# Ricky_and_Min_Lin_-_ART_Robot.net
KiCad netlist of a schematic drawn in Altium Designer
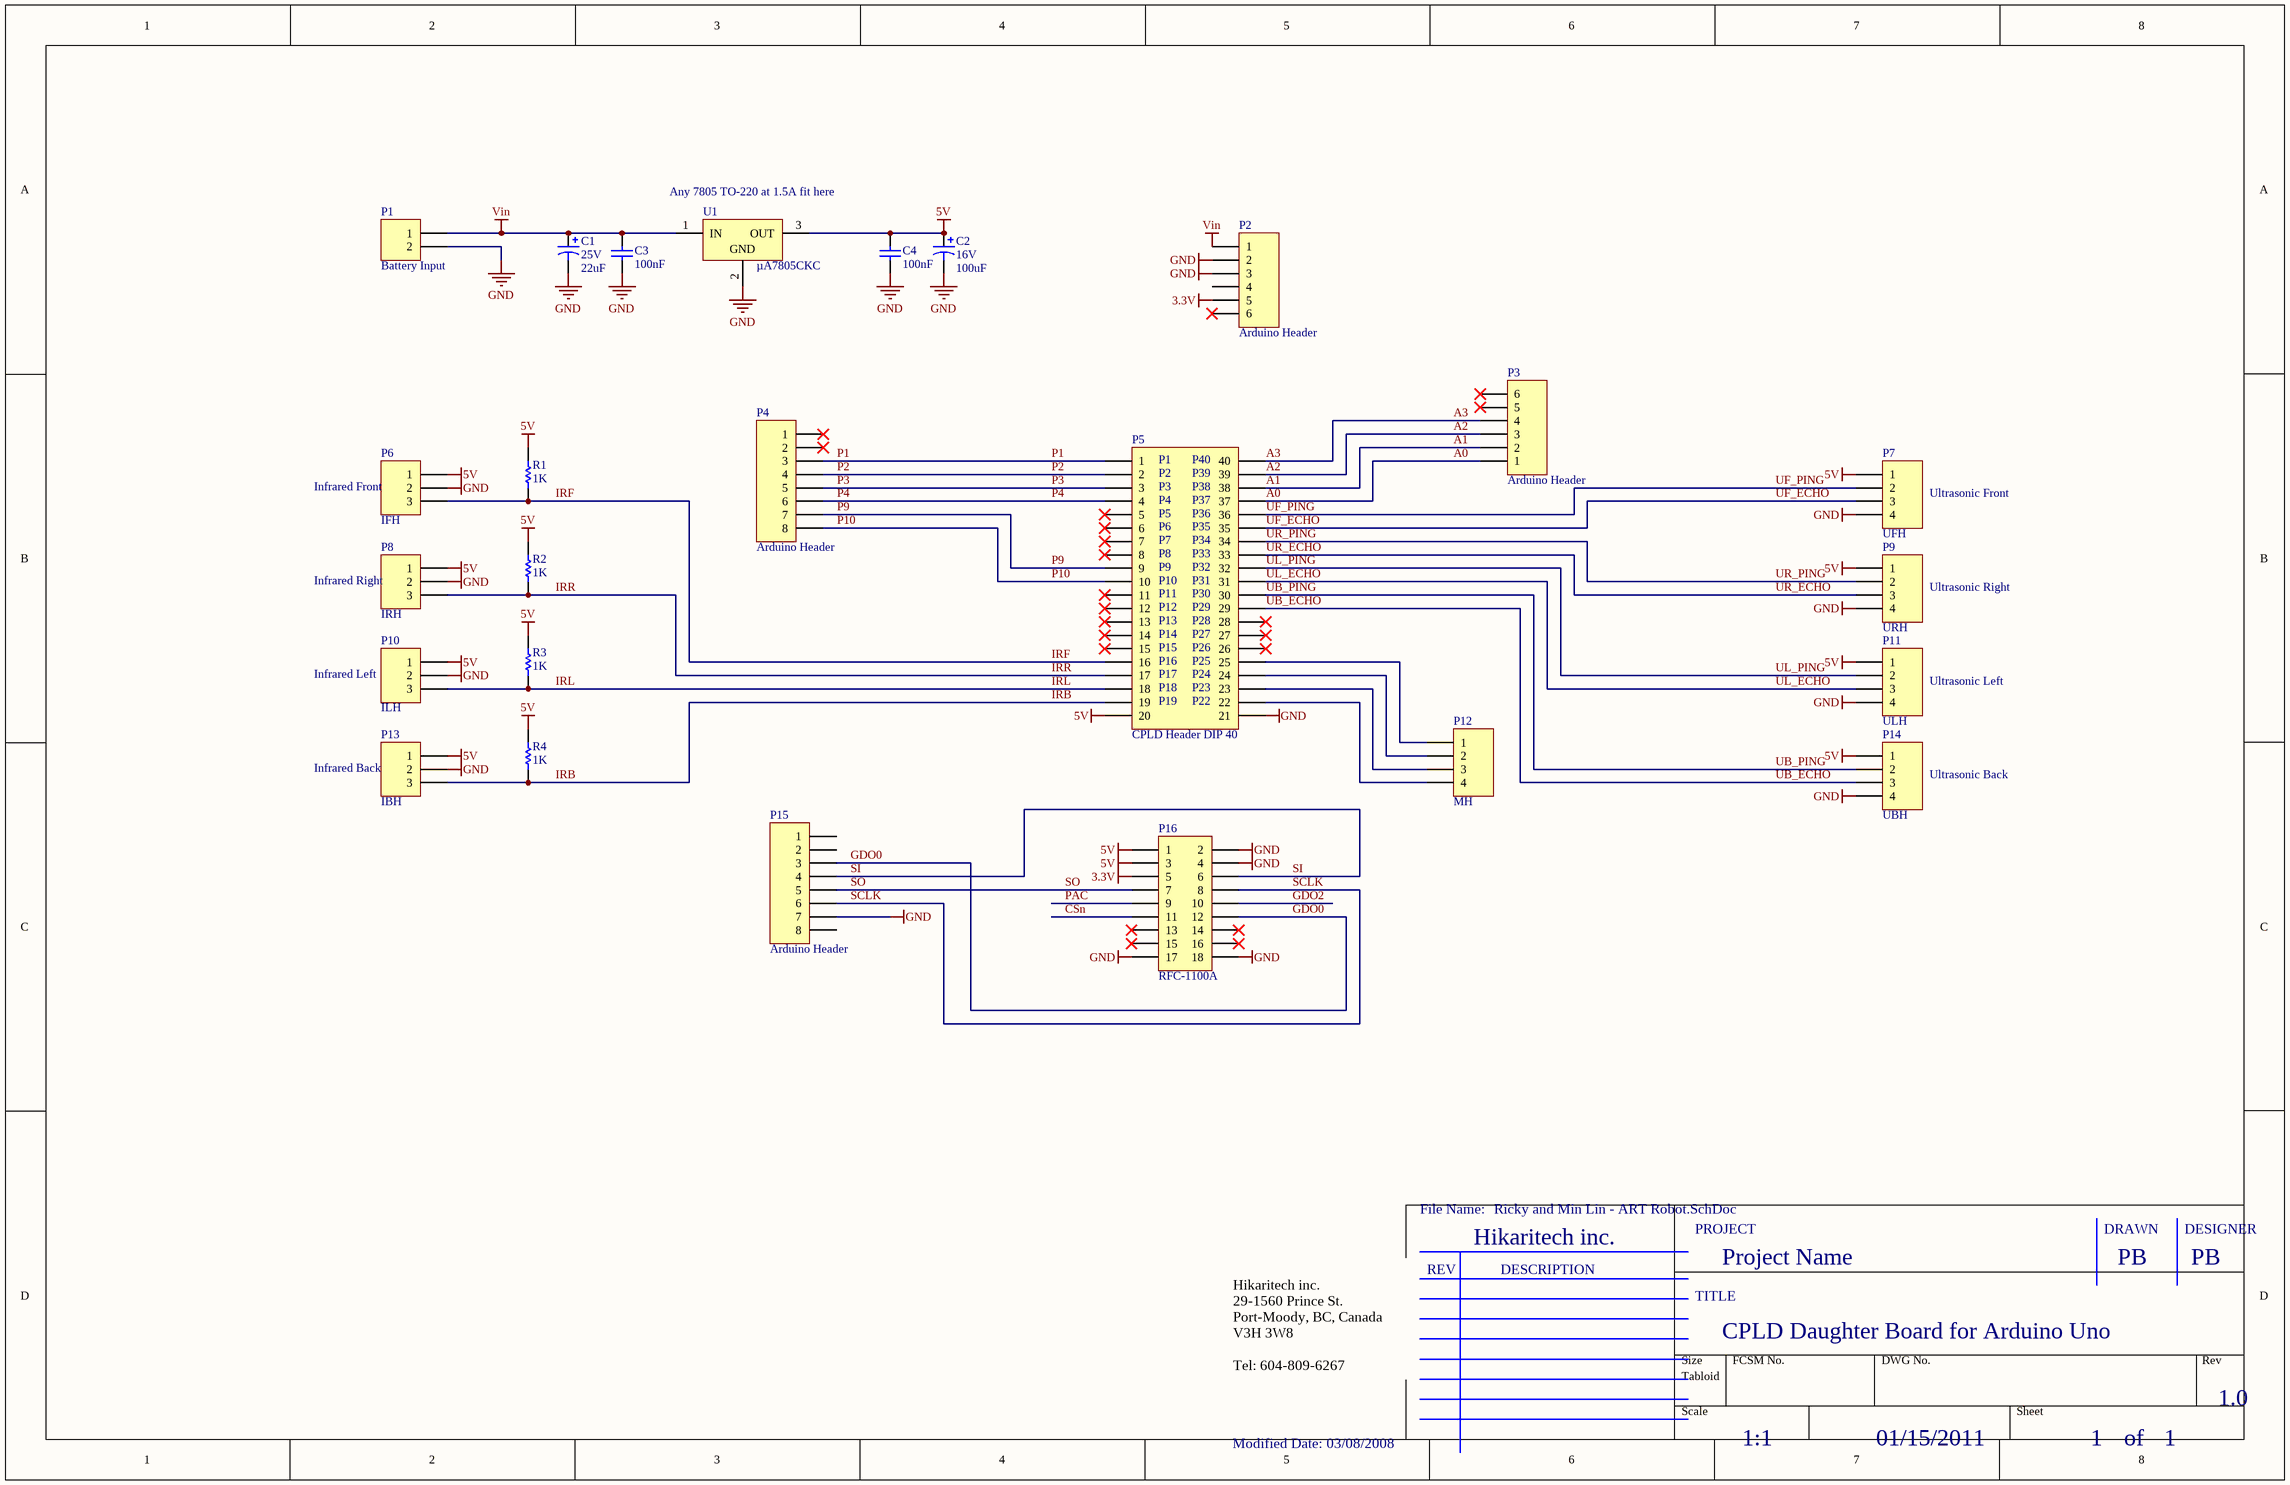
[diagram p0: Ricky and Min Lin - ART Robot.SchDoc]

(export (version "E")
  (design (tool "Eeschema 10.0.6"))
  (components
    (comp (ref "C1")
      (value "25V")
      (footprint "E")
      (description "Solid Aluminum Capacitor with Organic Semiconductor Electrolyte: 22uF, 25V, Bulk Pack")
      (fields (field (name "ALTIUM_VALUE") "22uF") (field (name "PUBLISHER") "Altium Limited"))
      (libsource (lib "Vishay Electrolytic Radial-Lead Capacitor") (part "94SC226X0025EBP"))
    )
    (comp (ref "C2")
      (value "16V")
      (footprint "E")
      (description "Solid Aluminum Capacitor with Organic Semiconductor Electrolyte: 100uF, 16V, Bulk Pack")
      (fields (field (name "ALTIUM_VALUE") "100uF") (field (name "PUBLISHER") "Altium Limited"))
      (libsource (lib "Vishay Electrolytic Radial-Lead Capacitor") (part "94SH107X0016EBP"))
    )
    (comp (ref "C3")
      (value "100nF")
      (footprint "VP41-2.5")
      (description "Dipped Radial Multilayer Ceramic Capacitor X7R: 100nF")
      (fields (field (name "Comment") "VP41BY104") (field (name "PUBLISHER") "Altium Limited"))
      (libsource (lib "Vishay Vitramon Ceramic Dipped Capacitor") (part "VP41BY104"))
    )
    (comp (ref "C4")
      (value "100nF")
      (footprint "VP41-2.5")
      (description "Dipped Radial Multilayer Ceramic Capacitor X7R: 100nF")
      (fields (field (name "Comment") "VP41BY104") (field (name "PUBLISHER") "Altium Limited"))
      (libsource (lib "Vishay Vitramon Ceramic Dipped Capacitor") (part "VP41BY104"))
    )
    (comp (ref "P1")
      (value "Battery Input")
      (footprint "HDR1X2H")
      (description "CONN 2 PINS 2.54mm Wire to Board Latch RA Tin")
      (fields (field (name "MANUFACTURER") "CKMOLD") (field (name "MANUFACTURER PART NUMBER") "25430202"))
      (libsource (lib "ART Robot") (part "CONN 2 PIN 2.54mm Latch RA Tin"))
    )
    (comp (ref "P2")
      (value "Arduino Header")
      (footprint "HDR1X6")
      (description "Header, 6-Pin")
      (fields (field (name "PUBLISHER") "Altium Limited"))
      (libsource (lib "Miscellaneous Connectors") (part "Header 6"))
    )
    (comp (ref "P3")
      (value "Arduino Header")
      (footprint "HDR1X6")
      (description "Header, 6-Pin")
      (fields (field (name "PUBLISHER") "Altium Limited"))
      (libsource (lib "") (part "Header 6_1"))
    )
    (comp (ref "P4")
      (value "Arduino Header")
      (footprint "HDR1X8")
      (description "Header, 8-Pin")
      (fields (field (name "PUBLISHER") "Altium Limited"))
      (libsource (lib "Miscellaneous Connectors") (part "Header 8"))
    )
    (comp (ref "P5")
      (value "CPLD Header DIP 40")
      (footprint "DIP-40")
      (description "Header, 20-Pin, Dual row")
      (fields (field (name "PUBLISHER") "Altium Limited"))
      (libsource (lib "ART Robot") (part "Header DIP 40"))
    )
    (comp (ref "P6")
      (value "IFH")
      (footprint "HDR1X3H")
      (description "CONN 3 PINS 2.54mm Wire to Board Latch RA Tin")
      (fields (field (name "MANUFACTURER") "CKMOLD") (field (name "MANUFACTURER PART NUMBER") "25430202"))
      (libsource (lib "ART Robot") (part "CONN 3 PIN 2.54mm Latch RA Tin"))
    )
    (comp (ref "P7")
      (value "UFH")
      (footprint "HDR1X4H")
      (description "CONN 4 PINS 2.54mm Wire to Board Latch RA Tin")
      (fields (field (name "MANUFACTURER") "CKMOLD") (field (name "MANUFACTURER PART NUMBER") "25430202"))
      (libsource (lib "ART Robot") (part "CONN 4 PIN 2.54mm Latch RA Tin"))
    )
    (comp (ref "P8")
      (value "IRH")
      (footprint "HDR1X3H")
      (description "CONN 3 PINS 2.54mm Wire to Board Latch RA Tin")
      (fields (field (name "MANUFACTURER") "CKMOLD") (field (name "MANUFACTURER PART NUMBER") "25430202"))
      (libsource (lib "ART Robot") (part "CONN 3 PIN 2.54mm Latch RA Tin"))
    )
    (comp (ref "P9")
      (value "URH")
      (footprint "HDR1X4H")
      (description "CONN 4 PINS 2.54mm Wire to Board Latch RA Tin")
      (fields (field (name "MANUFACTURER") "CKMOLD") (field (name "MANUFACTURER PART NUMBER") "25430202"))
      (libsource (lib "ART Robot") (part "CONN 4 PIN 2.54mm Latch RA Tin"))
    )
    (comp (ref "P10")
      (value "ILH")
      (footprint "HDR1X3H")
      (description "CONN 3 PINS 2.54mm Wire to Board Latch RA Tin")
      (fields (field (name "MANUFACTURER") "CKMOLD") (field (name "MANUFACTURER PART NUMBER") "25430202"))
      (libsource (lib "ART Robot") (part "CONN 3 PIN 2.54mm Latch RA Tin"))
    )
    (comp (ref "P11")
      (value "ULH")
      (footprint "HDR1X4H")
      (description "CONN 4 PINS 2.54mm Wire to Board Latch RA Tin")
      (fields (field (name "MANUFACTURER") "CKMOLD") (field (name "MANUFACTURER PART NUMBER") "25430202"))
      (libsource (lib "ART Robot") (part "CONN 4 PIN 2.54mm Latch RA Tin"))
    )
    (comp (ref "P12")
      (value "MH")
      (footprint "HDR1X4")
      (description "Header, 4-Pin")
      (fields (field (name "PUBLISHER") "Altium Limited"))
      (libsource (lib "Miscellaneous Connectors") (part "Header 4"))
    )
    (comp (ref "P13")
      (value "IBH")
      (footprint "HDR1X3H")
      (description "CONN 3 PINS 2.54mm Wire to Board Latch RA Tin")
      (fields (field (name "MANUFACTURER") "CKMOLD") (field (name "MANUFACTURER PART NUMBER") "25430202"))
      (libsource (lib "ART Robot") (part "CONN 3 PIN 2.54mm Latch RA Tin"))
    )
    (comp (ref "P14")
      (value "UBH")
      (footprint "HDR1X4H")
      (description "CONN 4 PINS 2.54mm Wire to Board Latch RA Tin")
      (fields (field (name "MANUFACTURER") "CKMOLD") (field (name "MANUFACTURER PART NUMBER") "25430202"))
      (libsource (lib "ART Robot") (part "CONN 4 PIN 2.54mm Latch RA Tin"))
    )
    (comp (ref "P15")
      (value "Arduino Header")
      (footprint "HDR1X8")
      (description "Header, 8-Pin")
      (fields (field (name "PUBLISHER") "Altium Limited"))
      (libsource (lib "Miscellaneous Connectors") (part "Header 8"))
    )
    (comp (ref "P16")
      (value "RFC-1100A")
      (footprint "HDR2X9")
      (description "Header, 9-Pin, Dual row")
      (fields (field (name "PUBLISHER") "Altium Limited"))
      (libsource (lib "Miscellaneous Connectors") (part "Header 9X2"))
    )
    (comp (ref "R1")
      (value "1K")
      (footprint "AXIAL-0.3")
      (description "Resistor")
      (fields (field (name "Comment") "Res1") (field (name "PUBLISHER") "Altium Limited"))
      (libsource (lib "Miscellaneous Devices") (part "Res1"))
    )
    (comp (ref "R2")
      (value "1K")
      (footprint "AXIAL-0.3")
      (description "Resistor")
      (fields (field (name "Comment") "Res1") (field (name "PUBLISHER") "Altium Limited"))
      (libsource (lib "Miscellaneous Devices") (part "Res1"))
    )
    (comp (ref "R3")
      (value "1K")
      (footprint "AXIAL-0.3")
      (description "Resistor")
      (fields (field (name "Comment") "Res1") (field (name "PUBLISHER") "Altium Limited"))
      (libsource (lib "Miscellaneous Devices") (part "Res1"))
    )
    (comp (ref "R4")
      (value "1K")
      (footprint "AXIAL-0.3")
      (description "Resistor")
      (fields (field (name "Comment") "Res1") (field (name "PUBLISHER") "Altium Limited"))
      (libsource (lib "Miscellaneous Devices") (part "Res1"))
    )
    (comp (ref "U1")
      (value "µA7805CKC")
      (footprint "KC03")
      (description "Positive-Voltage Regulator")
      (fields (field (name "PUBLISHER") "Altium Limited"))
      (libsource (lib "TI Power Mgt Voltage Regulator") (part "µA7805CKC"))
    )
  )
  (nets
    (net (code "1") (name "/A0") (class "Default")
      (node (ref "P3") (pin "1") (pinfunction "1_1") (pintype "passive"))
      (node (ref "P5") (pin "37") (pinfunction "37_37") (pintype "passive"))
    )
    (net (code "2") (name "/A1") (class "Default")
      (node (ref "P3") (pin "2") (pinfunction "2_2") (pintype "passive"))
      (node (ref "P5") (pin "38") (pinfunction "38_38") (pintype "passive"))
    )
    (net (code "3") (name "/A2") (class "Default")
      (node (ref "P3") (pin "3") (pinfunction "3_3") (pintype "passive"))
      (node (ref "P5") (pin "39") (pinfunction "39_39") (pintype "passive"))
    )
    (net (code "4") (name "/A3") (class "Default")
      (node (ref "P3") (pin "4") (pinfunction "4_4") (pintype "passive"))
      (node (ref "P5") (pin "40") (pinfunction "40_40") (pintype "passive"))
    )
    (net (code "5") (name "/CSn") (class "Default")
      (node (ref "P16") (pin "11") (pinfunction "11_11") (pintype "passive"))
    )
    (net (code "6") (name "/GDO0") (class "Default")
      (node (ref "P15") (pin "3") (pinfunction "3_3") (pintype "passive"))
      (node (ref "P16") (pin "12") (pinfunction "12_12") (pintype "passive"))
    )
    (net (code "7") (name "/GDO2") (class "Default")
      (node (ref "P16") (pin "10") (pinfunction "10_10") (pintype "passive"))
    )
    (net (code "8") (name "/IRB") (class "Default")
      (node (ref "P13") (pin "3") (pinfunction "3_3") (pintype "passive"))
      (node (ref "P5") (pin "19") (pinfunction "19_19") (pintype "passive"))
      (node (ref "R4") (pin "1") (pinfunction "1_1") (pintype "passive"))
    )
    (net (code "9") (name "/IRF") (class "Default")
      (node (ref "P5") (pin "16") (pinfunction "16_16") (pintype "passive"))
      (node (ref "P6") (pin "3") (pinfunction "3_3") (pintype "passive"))
      (node (ref "R1") (pin "1") (pinfunction "1_1") (pintype "passive"))
    )
    (net (code "10") (name "/IRL") (class "Default")
      (node (ref "P10") (pin "3") (pinfunction "3_3") (pintype "passive"))
      (node (ref "P5") (pin "18") (pinfunction "18_18") (pintype "passive"))
      (node (ref "R3") (pin "1") (pinfunction "1_1") (pintype "passive"))
    )
    (net (code "11") (name "/IRR") (class "Default")
      (node (ref "P5") (pin "17") (pinfunction "17_17") (pintype "passive"))
      (node (ref "P8") (pin "3") (pinfunction "3_3") (pintype "passive"))
      (node (ref "R2") (pin "1") (pinfunction "1_1") (pintype "passive"))
    )
    (net (code "12") (name "/P1") (class "Default")
      (node (ref "P4") (pin "3") (pinfunction "3_3") (pintype "passive"))
      (node (ref "P5") (pin "1") (pinfunction "1_1") (pintype "passive"))
    )
    (net (code "13") (name "/P2") (class "Default")
      (node (ref "P4") (pin "4") (pinfunction "4_4") (pintype "passive"))
      (node (ref "P5") (pin "2") (pinfunction "2_2") (pintype "passive"))
    )
    (net (code "14") (name "/P3") (class "Default")
      (node (ref "P4") (pin "5") (pinfunction "5_5") (pintype "passive"))
      (node (ref "P5") (pin "3") (pinfunction "3_3") (pintype "passive"))
    )
    (net (code "15") (name "/P4") (class "Default")
      (node (ref "P4") (pin "6") (pinfunction "6_6") (pintype "passive"))
      (node (ref "P5") (pin "4") (pinfunction "4_4") (pintype "passive"))
    )
    (net (code "16") (name "/P9") (class "Default")
      (node (ref "P4") (pin "7") (pinfunction "7_7") (pintype "passive"))
      (node (ref "P5") (pin "9") (pinfunction "9_9") (pintype "passive"))
    )
    (net (code "17") (name "/P10") (class "Default")
      (node (ref "P4") (pin "8") (pinfunction "8_8") (pintype "passive"))
      (node (ref "P5") (pin "10") (pinfunction "10_10") (pintype "passive"))
    )
    (net (code "18") (name "/PAC") (class "Default")
      (node (ref "P16") (pin "9") (pinfunction "9_9") (pintype "passive"))
    )
    (net (code "19") (name "/SCLK") (class "Default")
      (node (ref "P15") (pin "6") (pinfunction "6_6") (pintype "passive"))
      (node (ref "P16") (pin "8") (pinfunction "8_8") (pintype "passive"))
    )
    (net (code "20") (name "/SI") (class "Default")
      (node (ref "P15") (pin "4") (pinfunction "4_4") (pintype "passive"))
      (node (ref "P16") (pin "6") (pinfunction "6_6") (pintype "passive"))
    )
    (net (code "21") (name "/SO") (class "Default")
      (node (ref "P15") (pin "5") (pinfunction "5_5") (pintype "passive"))
      (node (ref "P16") (pin "7") (pinfunction "7_7") (pintype "passive"))
    )
    (net (code "22") (name "/UB_ECHO") (class "Default")
      (node (ref "P14") (pin "3") (pinfunction "3_3") (pintype "passive"))
      (node (ref "P5") (pin "29") (pinfunction "29_29") (pintype "passive"))
    )
    (net (code "23") (name "/UB_PING") (class "Default")
      (node (ref "P14") (pin "2") (pinfunction "2_2") (pintype "passive"))
      (node (ref "P5") (pin "30") (pinfunction "30_30") (pintype "passive"))
    )
    (net (code "24") (name "/UF_ECHO") (class "Default")
      (node (ref "P5") (pin "35") (pinfunction "35_35") (pintype "passive"))
      (node (ref "P7") (pin "3") (pinfunction "3_3") (pintype "passive"))
    )
    (net (code "25") (name "/UF_PING") (class "Default")
      (node (ref "P5") (pin "36") (pinfunction "36_36") (pintype "passive"))
      (node (ref "P7") (pin "2") (pinfunction "2_2") (pintype "passive"))
    )
    (net (code "26") (name "/UL_ECHO") (class "Default")
      (node (ref "P11") (pin "3") (pinfunction "3_3") (pintype "passive"))
      (node (ref "P5") (pin "31") (pinfunction "31_31") (pintype "passive"))
    )
    (net (code "27") (name "/UL_PING") (class "Default")
      (node (ref "P11") (pin "2") (pinfunction "2_2") (pintype "passive"))
      (node (ref "P5") (pin "32") (pinfunction "32_32") (pintype "passive"))
    )
    (net (code "28") (name "/UR_ECHO") (class "Default")
      (node (ref "P5") (pin "33") (pinfunction "33_33") (pintype "passive"))
      (node (ref "P9") (pin "3") (pinfunction "3_3") (pintype "passive"))
    )
    (net (code "29") (name "/UR_PING") (class "Default")
      (node (ref "P5") (pin "34") (pinfunction "34_34") (pintype "passive"))
      (node (ref "P9") (pin "2") (pinfunction "2_2") (pintype "passive"))
    )
    (net (code "30") (name "3.3V") (class "Default")
      (node (ref "P16") (pin "5") (pinfunction "5_5") (pintype "passive"))
      (node (ref "P2") (pin "5") (pinfunction "5_5") (pintype "passive"))
    )
    (net (code "31") (name "5V") (class "Default")
      (node (ref "C2") (pin "1") (pinfunction "1_1") (pintype "passive"))
      (node (ref "C4") (pin "1") (pinfunction "1_1") (pintype "passive"))
      (node (ref "P10") (pin "1") (pinfunction "1_1") (pintype "passive"))
      (node (ref "P11") (pin "1") (pinfunction "1_1") (pintype "passive"))
      (node (ref "P13") (pin "1") (pinfunction "1_1") (pintype "passive"))
      (node (ref "P14") (pin "1") (pinfunction "1_1") (pintype "passive"))
      (node (ref "P16") (pin "1") (pinfunction "1_1") (pintype "passive"))
      (node (ref "P16") (pin "3") (pinfunction "3_3") (pintype "passive"))
      (node (ref "P5") (pin "20") (pinfunction "20_20") (pintype "passive"))
      (node (ref "P6") (pin "1") (pinfunction "1_1") (pintype "passive"))
      (node (ref "P7") (pin "1") (pinfunction "1_1") (pintype "passive"))
      (node (ref "P8") (pin "1") (pinfunction "1_1") (pintype "passive"))
      (node (ref "P9") (pin "1") (pinfunction "1_1") (pintype "passive"))
      (node (ref "R1") (pin "2") (pinfunction "2_2") (pintype "passive"))
      (node (ref "R2") (pin "2") (pinfunction "2_2") (pintype "passive"))
      (node (ref "R3") (pin "2") (pinfunction "2_2") (pintype "passive"))
      (node (ref "R4") (pin "2") (pinfunction "2_2") (pintype "passive"))
      (node (ref "U1") (pin "3") (pinfunction "OUT_3") (pintype "power_in"))
    )
    (net (code "32") (name "GND") (class "Default")
      (node (ref "C1") (pin "2") (pinfunction "2_2") (pintype "passive"))
      (node (ref "C2") (pin "2") (pinfunction "2_2") (pintype "passive"))
      (node (ref "C3") (pin "2") (pinfunction "2_2") (pintype "passive"))
      (node (ref "C4") (pin "2") (pinfunction "2_2") (pintype "passive"))
      (node (ref "P1") (pin "2") (pinfunction "2_2") (pintype "passive"))
      (node (ref "P10") (pin "2") (pinfunction "2_2") (pintype "passive"))
      (node (ref "P11") (pin "4") (pinfunction "4_4") (pintype "passive"))
      (node (ref "P13") (pin "2") (pinfunction "2_2") (pintype "passive"))
      (node (ref "P14") (pin "4") (pinfunction "4_4") (pintype "passive"))
      (node (ref "P15") (pin "7") (pinfunction "7_7") (pintype "passive"))
      (node (ref "P16") (pin "17") (pinfunction "17_17") (pintype "passive"))
      (node (ref "P16") (pin "18") (pinfunction "18_18") (pintype "passive"))
      (node (ref "P16") (pin "2") (pinfunction "2_2") (pintype "passive"))
      (node (ref "P16") (pin "4") (pinfunction "4_4") (pintype "passive"))
      (node (ref "P2") (pin "2") (pinfunction "2_2") (pintype "passive"))
      (node (ref "P2") (pin "3") (pinfunction "3_3") (pintype "passive"))
      (node (ref "P5") (pin "21") (pinfunction "21_21") (pintype "passive"))
      (node (ref "P6") (pin "2") (pinfunction "2_2") (pintype "passive"))
      (node (ref "P7") (pin "4") (pinfunction "4_4") (pintype "passive"))
      (node (ref "P8") (pin "2") (pinfunction "2_2") (pintype "passive"))
      (node (ref "P9") (pin "4") (pinfunction "4_4") (pintype "passive"))
      (node (ref "U1") (pin "2") (pinfunction "GND_2") (pintype "power_in"))
    )
    (net (code "33") (name "Net-(P12-Pad1)") (class "Default")
      (node (ref "P12") (pin "1") (pinfunction "1_1") (pintype "passive"))
      (node (ref "P5") (pin "25") (pinfunction "25_25") (pintype "passive"))
    )
    (net (code "34") (name "Net-(P12-Pad2)") (class "Default")
      (node (ref "P12") (pin "2") (pinfunction "2_2") (pintype "passive"))
      (node (ref "P5") (pin "24") (pinfunction "24_24") (pintype "passive"))
    )
    (net (code "35") (name "Net-(P12-Pad3)") (class "Default")
      (node (ref "P12") (pin "3") (pinfunction "3_3") (pintype "passive"))
      (node (ref "P5") (pin "23") (pinfunction "23_23") (pintype "passive"))
    )
    (net (code "36") (name "Net-(P12-Pad4)") (class "Default")
      (node (ref "P12") (pin "4") (pinfunction "4_4") (pintype "passive"))
      (node (ref "P5") (pin "22") (pinfunction "22_22") (pintype "passive"))
    )
    (net (code "37") (name "Vin") (class "Default")
      (node (ref "C1") (pin "1") (pinfunction "1_1") (pintype "passive"))
      (node (ref "C3") (pin "1") (pinfunction "1_1") (pintype "passive"))
      (node (ref "P1") (pin "1") (pinfunction "1_1") (pintype "passive"))
      (node (ref "P2") (pin "1") (pinfunction "1_1") (pintype "passive"))
      (node (ref "U1") (pin "1") (pinfunction "IN_1") (pintype "power_in"))
    )
    (net (code "38") (name "unconnected-(P2-Pad4)") (class "Default")
      (node (ref "P2") (pin "4") (pinfunction "4_4") (pintype "passive"))
    )
    (net (code "39") (name "unconnected-(P2-Pad6)") (class "Default")
      (node (ref "P2") (pin "6") (pinfunction "6_6") (pintype "passive+no_connect"))
    )
    (net (code "40") (name "unconnected-(P3-Pad5)") (class "Default")
      (node (ref "P3") (pin "5") (pinfunction "5_5") (pintype "passive+no_connect"))
    )
    (net (code "41") (name "unconnected-(P3-Pad6)") (class "Default")
      (node (ref "P3") (pin "6") (pinfunction "6_6") (pintype "passive+no_connect"))
    )
    (net (code "42") (name "unconnected-(P4-Pad1)") (class "Default")
      (node (ref "P4") (pin "1") (pinfunction "1_1") (pintype "passive+no_connect"))
    )
    (net (code "43") (name "unconnected-(P4-Pad2)") (class "Default")
      (node (ref "P4") (pin "2") (pinfunction "2_2") (pintype "passive+no_connect"))
    )
    (net (code "44") (name "unconnected-(P5-Pad5)") (class "Default")
      (node (ref "P5") (pin "5") (pinfunction "5_5") (pintype "passive+no_connect"))
    )
    (net (code "45") (name "unconnected-(P5-Pad6)") (class "Default")
      (node (ref "P5") (pin "6") (pinfunction "6_6") (pintype "passive+no_connect"))
    )
    (net (code "46") (name "unconnected-(P5-Pad7)") (class "Default")
      (node (ref "P5") (pin "7") (pinfunction "7_7") (pintype "passive+no_connect"))
    )
    (net (code "47") (name "unconnected-(P5-Pad8)") (class "Default")
      (node (ref "P5") (pin "8") (pinfunction "8_8") (pintype "passive+no_connect"))
    )
    (net (code "48") (name "unconnected-(P5-Pad11)") (class "Default")
      (node (ref "P5") (pin "11") (pinfunction "11_11") (pintype "passive+no_connect"))
    )
    (net (code "49") (name "unconnected-(P5-Pad12)") (class "Default")
      (node (ref "P5") (pin "12") (pinfunction "12_12") (pintype "passive+no_connect"))
    )
    (net (code "50") (name "unconnected-(P5-Pad13)") (class "Default")
      (node (ref "P5") (pin "13") (pinfunction "13_13") (pintype "passive+no_connect"))
    )
    (net (code "51") (name "unconnected-(P5-Pad14)") (class "Default")
      (node (ref "P5") (pin "14") (pinfunction "14_14") (pintype "passive+no_connect"))
    )
    (net (code "52") (name "unconnected-(P5-Pad15)") (class "Default")
      (node (ref "P5") (pin "15") (pinfunction "15_15") (pintype "passive+no_connect"))
    )
    (net (code "53") (name "unconnected-(P5-Pad26)") (class "Default")
      (node (ref "P5") (pin "26") (pinfunction "26_26") (pintype "passive+no_connect"))
    )
    (net (code "54") (name "unconnected-(P5-Pad27)") (class "Default")
      (node (ref "P5") (pin "27") (pinfunction "27_27") (pintype "passive+no_connect"))
    )
    (net (code "55") (name "unconnected-(P5-Pad28)") (class "Default")
      (node (ref "P5") (pin "28") (pinfunction "28_28") (pintype "passive+no_connect"))
    )
    (net (code "56") (name "unconnected-(P15-Pad1)") (class "Default")
      (node (ref "P15") (pin "1") (pinfunction "1_1") (pintype "passive"))
    )
    (net (code "57") (name "unconnected-(P15-Pad2)") (class "Default")
      (node (ref "P15") (pin "2") (pinfunction "2_2") (pintype "passive"))
    )
    (net (code "58") (name "unconnected-(P15-Pad8)") (class "Default")
      (node (ref "P15") (pin "8") (pinfunction "8_8") (pintype "passive"))
    )
    (net (code "59") (name "unconnected-(P16-Pad13)") (class "Default")
      (node (ref "P16") (pin "13") (pinfunction "13_13") (pintype "passive+no_connect"))
    )
    (net (code "60") (name "unconnected-(P16-Pad14)") (class "Default")
      (node (ref "P16") (pin "14") (pinfunction "14_14") (pintype "passive+no_connect"))
    )
    (net (code "61") (name "unconnected-(P16-Pad15)") (class "Default")
      (node (ref "P16") (pin "15") (pinfunction "15_15") (pintype "passive+no_connect"))
    )
    (net (code "62") (name "unconnected-(P16-Pad16)") (class "Default")
      (node (ref "P16") (pin "16") (pinfunction "16_16") (pintype "passive+no_connect"))
    )
  )
)
